# attiniest85-batty-shield-mk-1_0.net
KiCad netlist of a schematic drawn in EAGLE
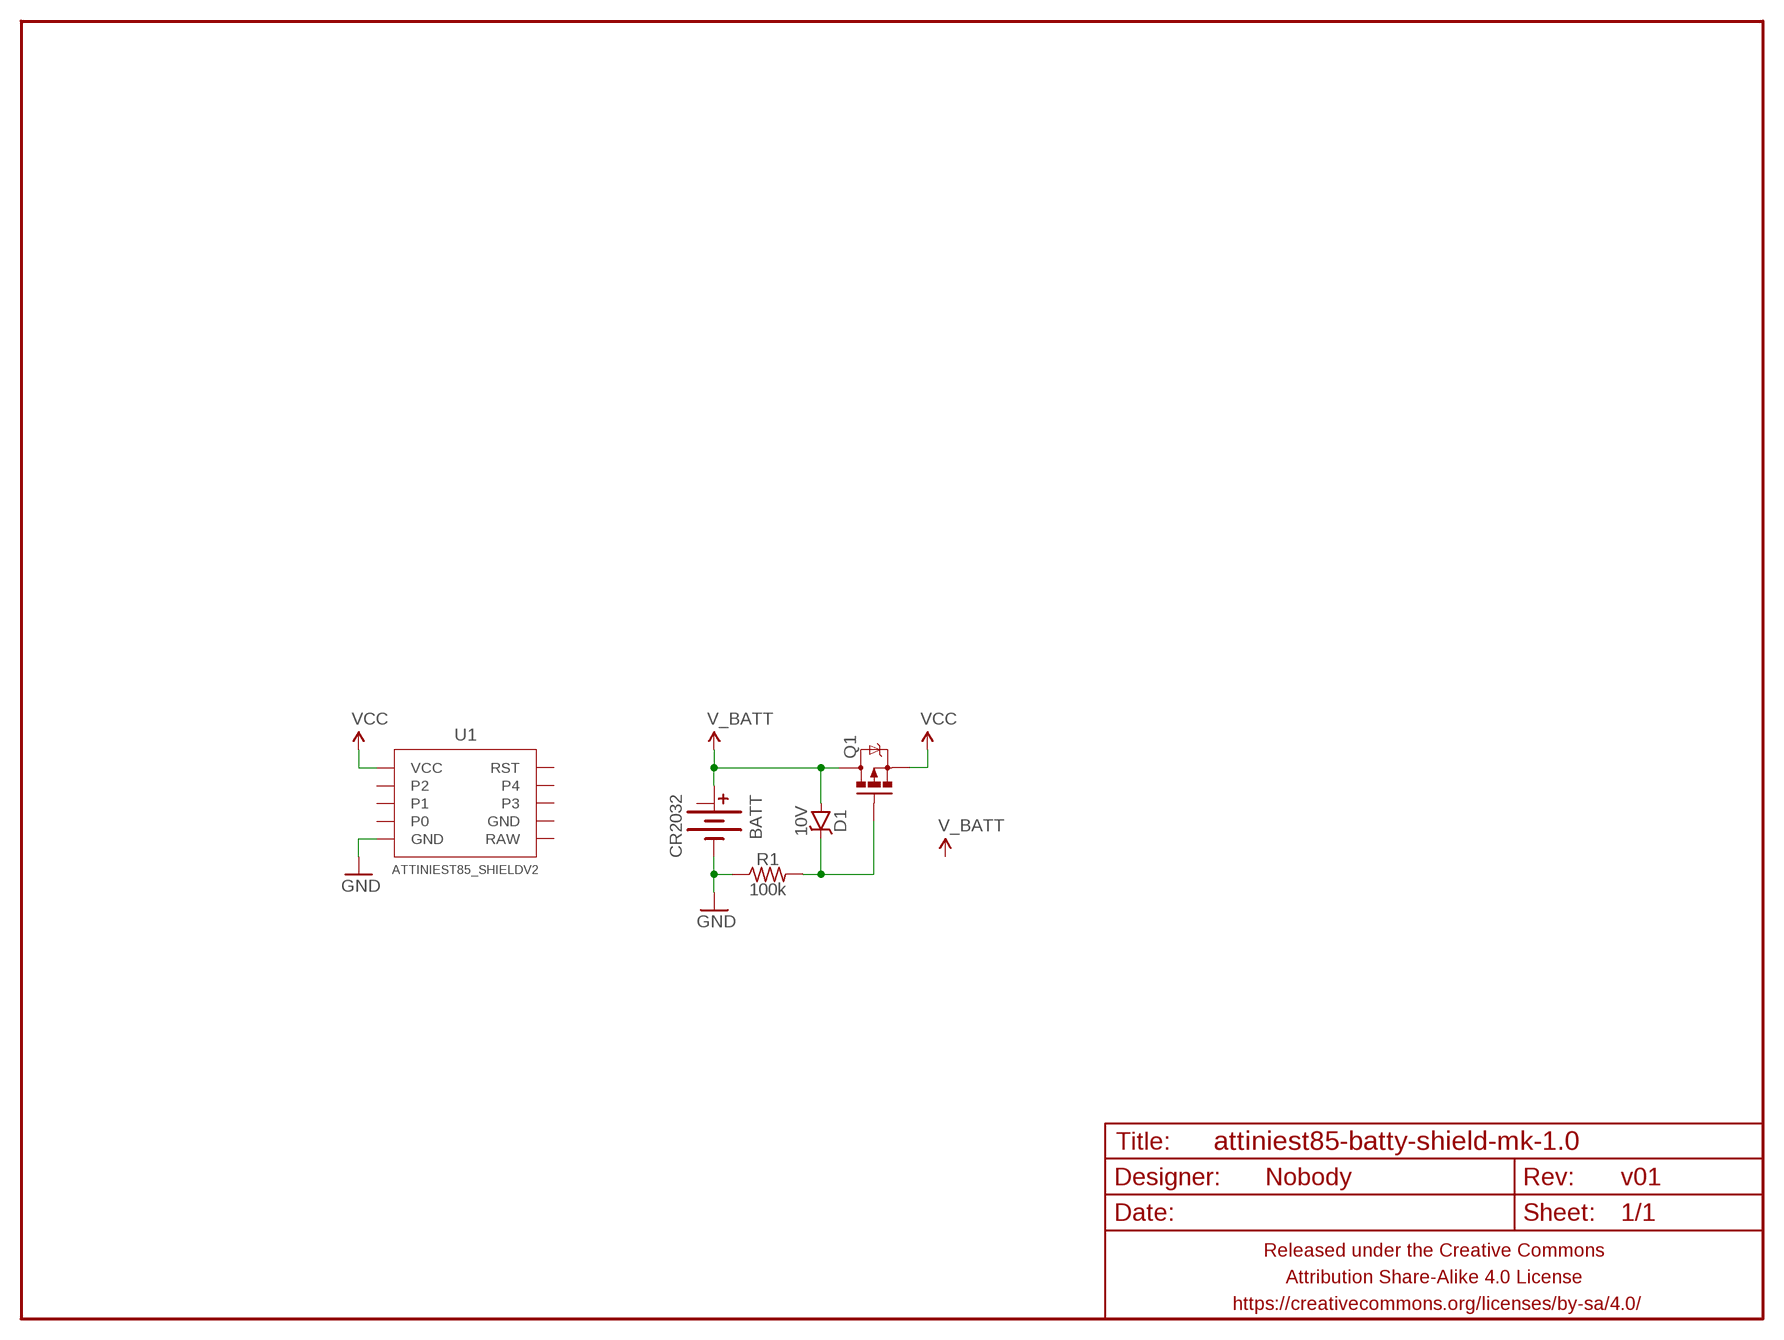
[diagram p0: schematic, sheet 1]

(export (version "E")
  (design (tool "Eeschema 10.0.6"))
  (components
    (comp (ref "BATT")
      (value "CR2032")
      (footprint "eagle-import:BATTCON_20MM_MINE")
      (libsource (lib "eagle-import") (part "BATTERY-COINCR2032_SMD"))
    )
    (comp (ref "D1")
      (value "10V")
      (footprint "eagle-import:DIODE-ZENNER-7.62MM")
      (libsource (lib "eagle-import") (part "DIODE-ZENER7.62MM-PTH"))
    )
    (comp (ref "FRAME1")
      (value "FRAME-LETTERNO_PACKAGE")
      (footprint "eagle-import:DUMMY")
      (fields (field (name "DESIGNER") "Nobody"))
      (libsource (lib "eagle-import") (part "FRAME-LETTERNO_PACKAGE"))
    )
    (comp (ref "Q1")
      (value "MOSFET-PCHANNELTO-92-INLINE-DGS")
      (footprint "eagle-import:TO-92-AMMO")
      (libsource (lib "eagle-import") (part "MOSFET-PCHANNELTO-92-INLINE-DGS"))
    )
    (comp (ref "R1")
      (value "100k")
      (footprint "eagle-import:RESISTOR-AXIAL-PTH-7.62MM")
      (libsource (lib "eagle-import") (part "RESISTORPTH-AXIAL-7.62MM"))
    )
    (comp (ref "U1")
      (value "ATTINIEST85_SHIELDV2")
      (footprint "eagle-import:ATTINIEST85_SHIELD_V2")
      (libsource (lib "eagle-import") (part "ATTINIEST85_SHIELDV2"))
    )
  )
  (nets
    (net (code "1") (name "GND") (class "Default")
      (node (ref "BATT") (pin "BOTTOM") (pinfunction "-_BOTTOM") (pintype "bidirectional"))
      (node (ref "R1") (pin "P$1") (pinfunction "1_P$1") (pintype "passive"))
      (node (ref "U1") (pin "GND@2") (pinfunction "GND_GND@2") (pintype "bidirectional"))
    )
    (net (code "2") (name "Net-(D1-C)") (class "Default")
      (node (ref "D1") (pin "K") (pinfunction "C_K") (pintype "passive"))
      (node (ref "Q1") (pin "2") (pinfunction "G_2") (pintype "passive"))
      (node (ref "R1") (pin "P$2") (pinfunction "2_P$2") (pintype "passive"))
    )
    (net (code "3") (name "VCC") (class "Default")
      (node (ref "Q1") (pin "3") (pinfunction "S_3") (pintype "passive"))
      (node (ref "U1") (pin "VCC") (pinfunction "VCC_VCC") (pintype "bidirectional"))
    )
    (net (code "4") (name "V_BATT") (class "Default")
      (node (ref "BATT") (pin "TOP@1") (pinfunction "+_TOP@1") (pintype "bidirectional"))
      (node (ref "D1") (pin "A") (pinfunction "A_A") (pintype "passive"))
      (node (ref "Q1") (pin "1") (pinfunction "D_1") (pintype "passive"))
    )
    (net (code "5") (name "unconnected-(BATT-+1-PadTOP@2)") (class "Default")
      (node (ref "BATT") (pin "TOP@2") (pinfunction "+1_TOP@2") (pintype "bidirectional"))
    )
    (net (code "6") (name "unconnected-(U1-GND-PadGND@1)") (class "Default")
      (node (ref "U1") (pin "GND@1") (pinfunction "GND_GND@1") (pintype "bidirectional"))
    )
    (net (code "7") (name "unconnected-(U1-P0-Pad0)") (class "Default")
      (node (ref "U1") (pin "0") (pinfunction "P0_0") (pintype "bidirectional"))
    )
    (net (code "8") (name "unconnected-(U1-P1-Pad1)") (class "Default")
      (node (ref "U1") (pin "1") (pinfunction "P1_1") (pintype "bidirectional"))
    )
    (net (code "9") (name "unconnected-(U1-P2-Pad2)") (class "Default")
      (node (ref "U1") (pin "2") (pinfunction "P2_2") (pintype "bidirectional"))
    )
    (net (code "10") (name "unconnected-(U1-P3-Pad3)") (class "Default")
      (node (ref "U1") (pin "3") (pinfunction "P3_3") (pintype "bidirectional"))
    )
    (net (code "11") (name "unconnected-(U1-P4-Pad4)") (class "Default")
      (node (ref "U1") (pin "4") (pinfunction "P4_4") (pintype "bidirectional"))
    )
    (net (code "12") (name "unconnected-(U1-PadRAW)") (class "Default")
      (node (ref "U1") (pin "RAW") (pinfunction "RAW_RAW") (pintype "bidirectional"))
    )
    (net (code "13") (name "unconnected-(U1-PadRST)") (class "Default")
      (node (ref "U1") (pin "RST") (pinfunction "RST_RST") (pintype "bidirectional"))
    )
  )
)
